# TwoStepPowerConversionBoard.net
KiCad netlist of a schematic drawn in EAGLE
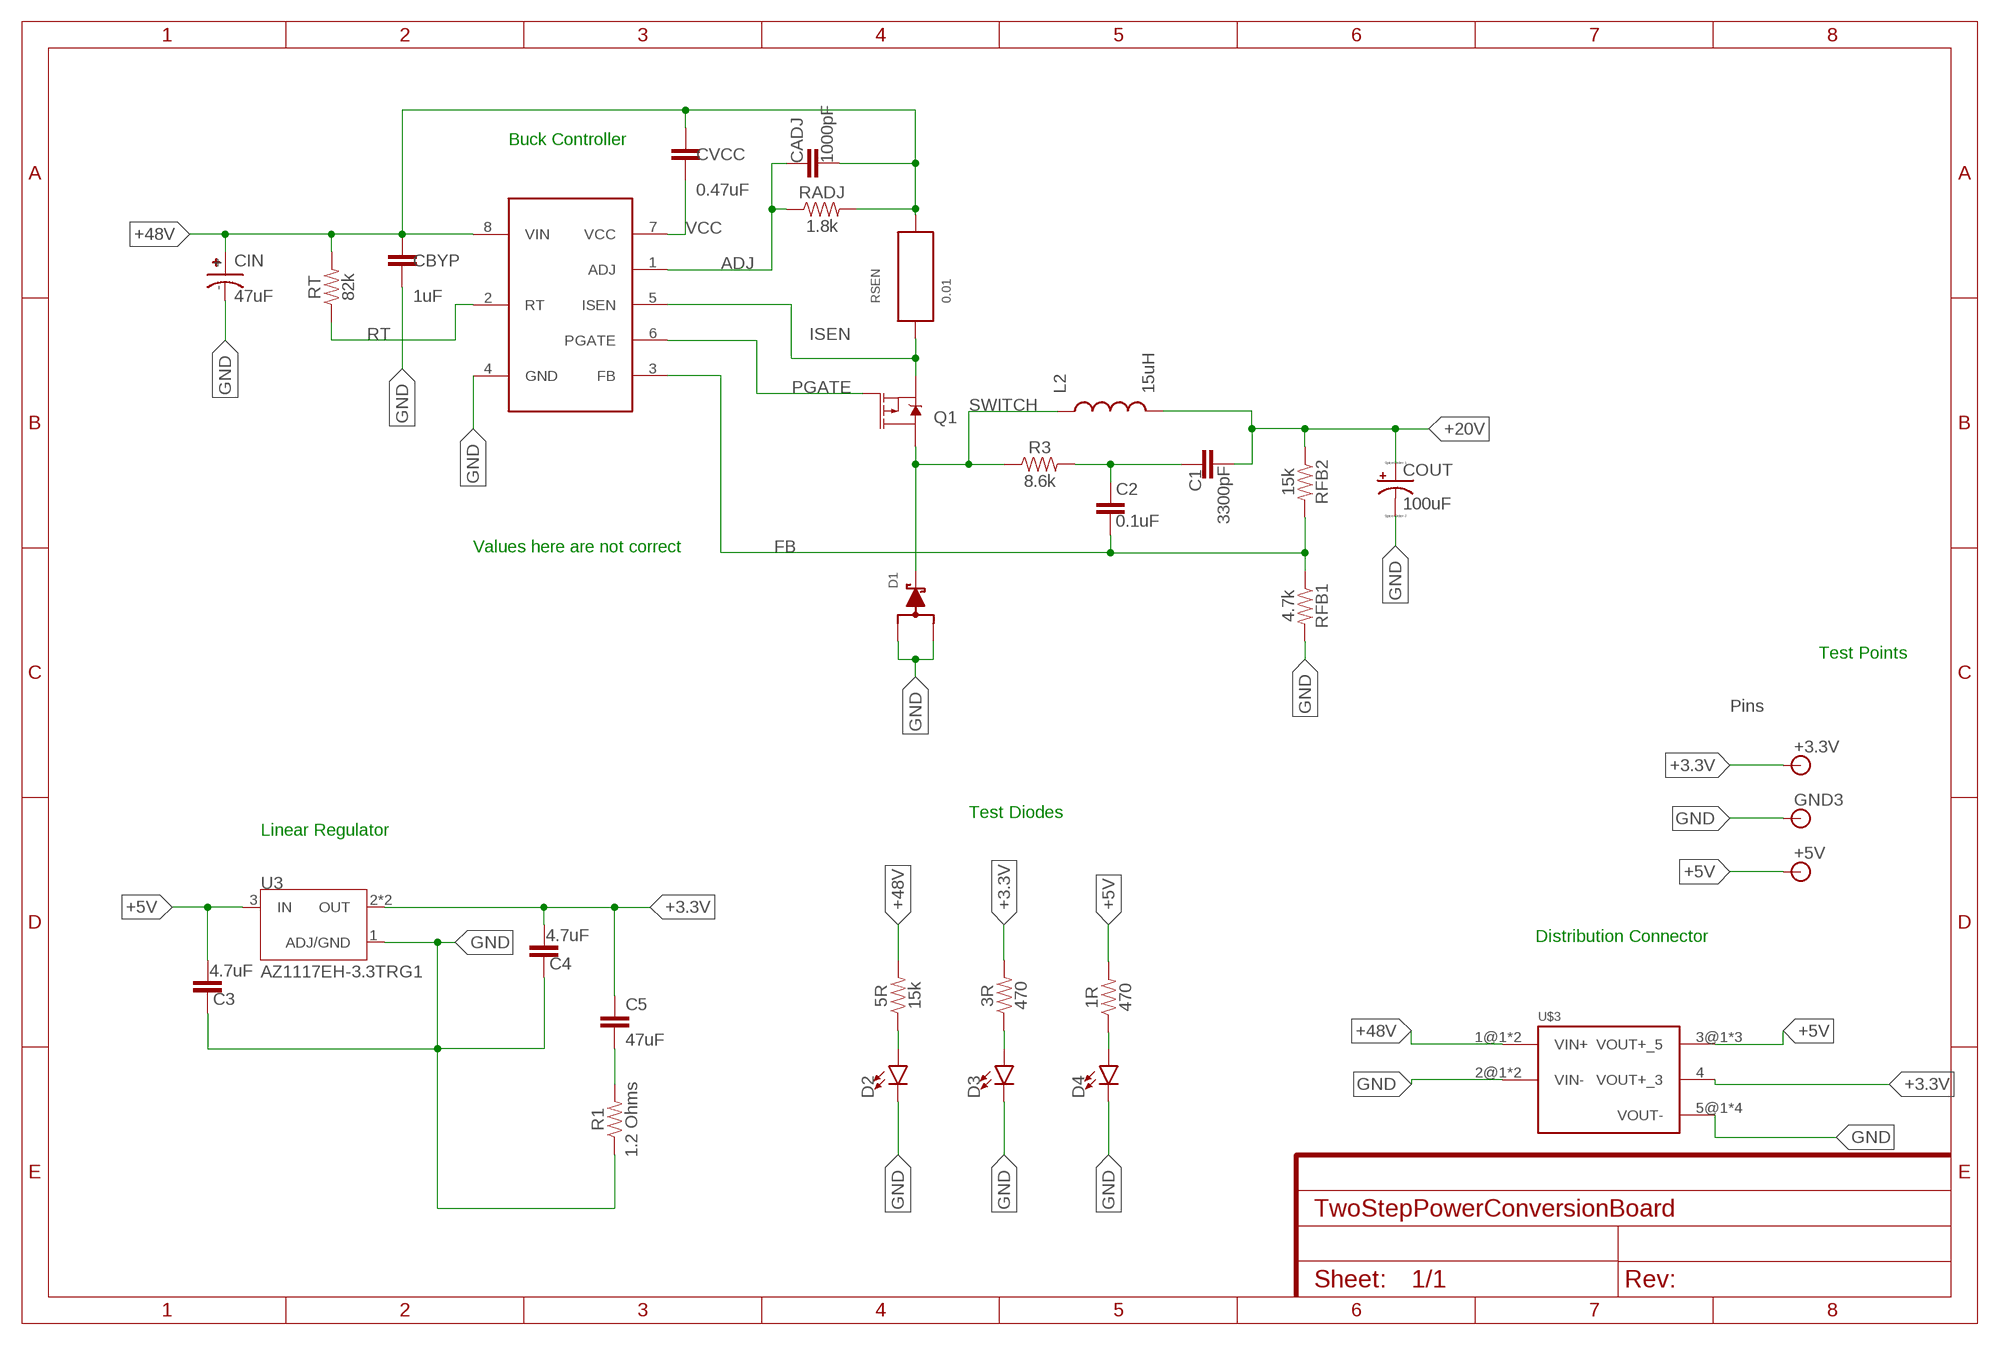
[diagram p0: schematic, sheet 1, part 1 of 2]
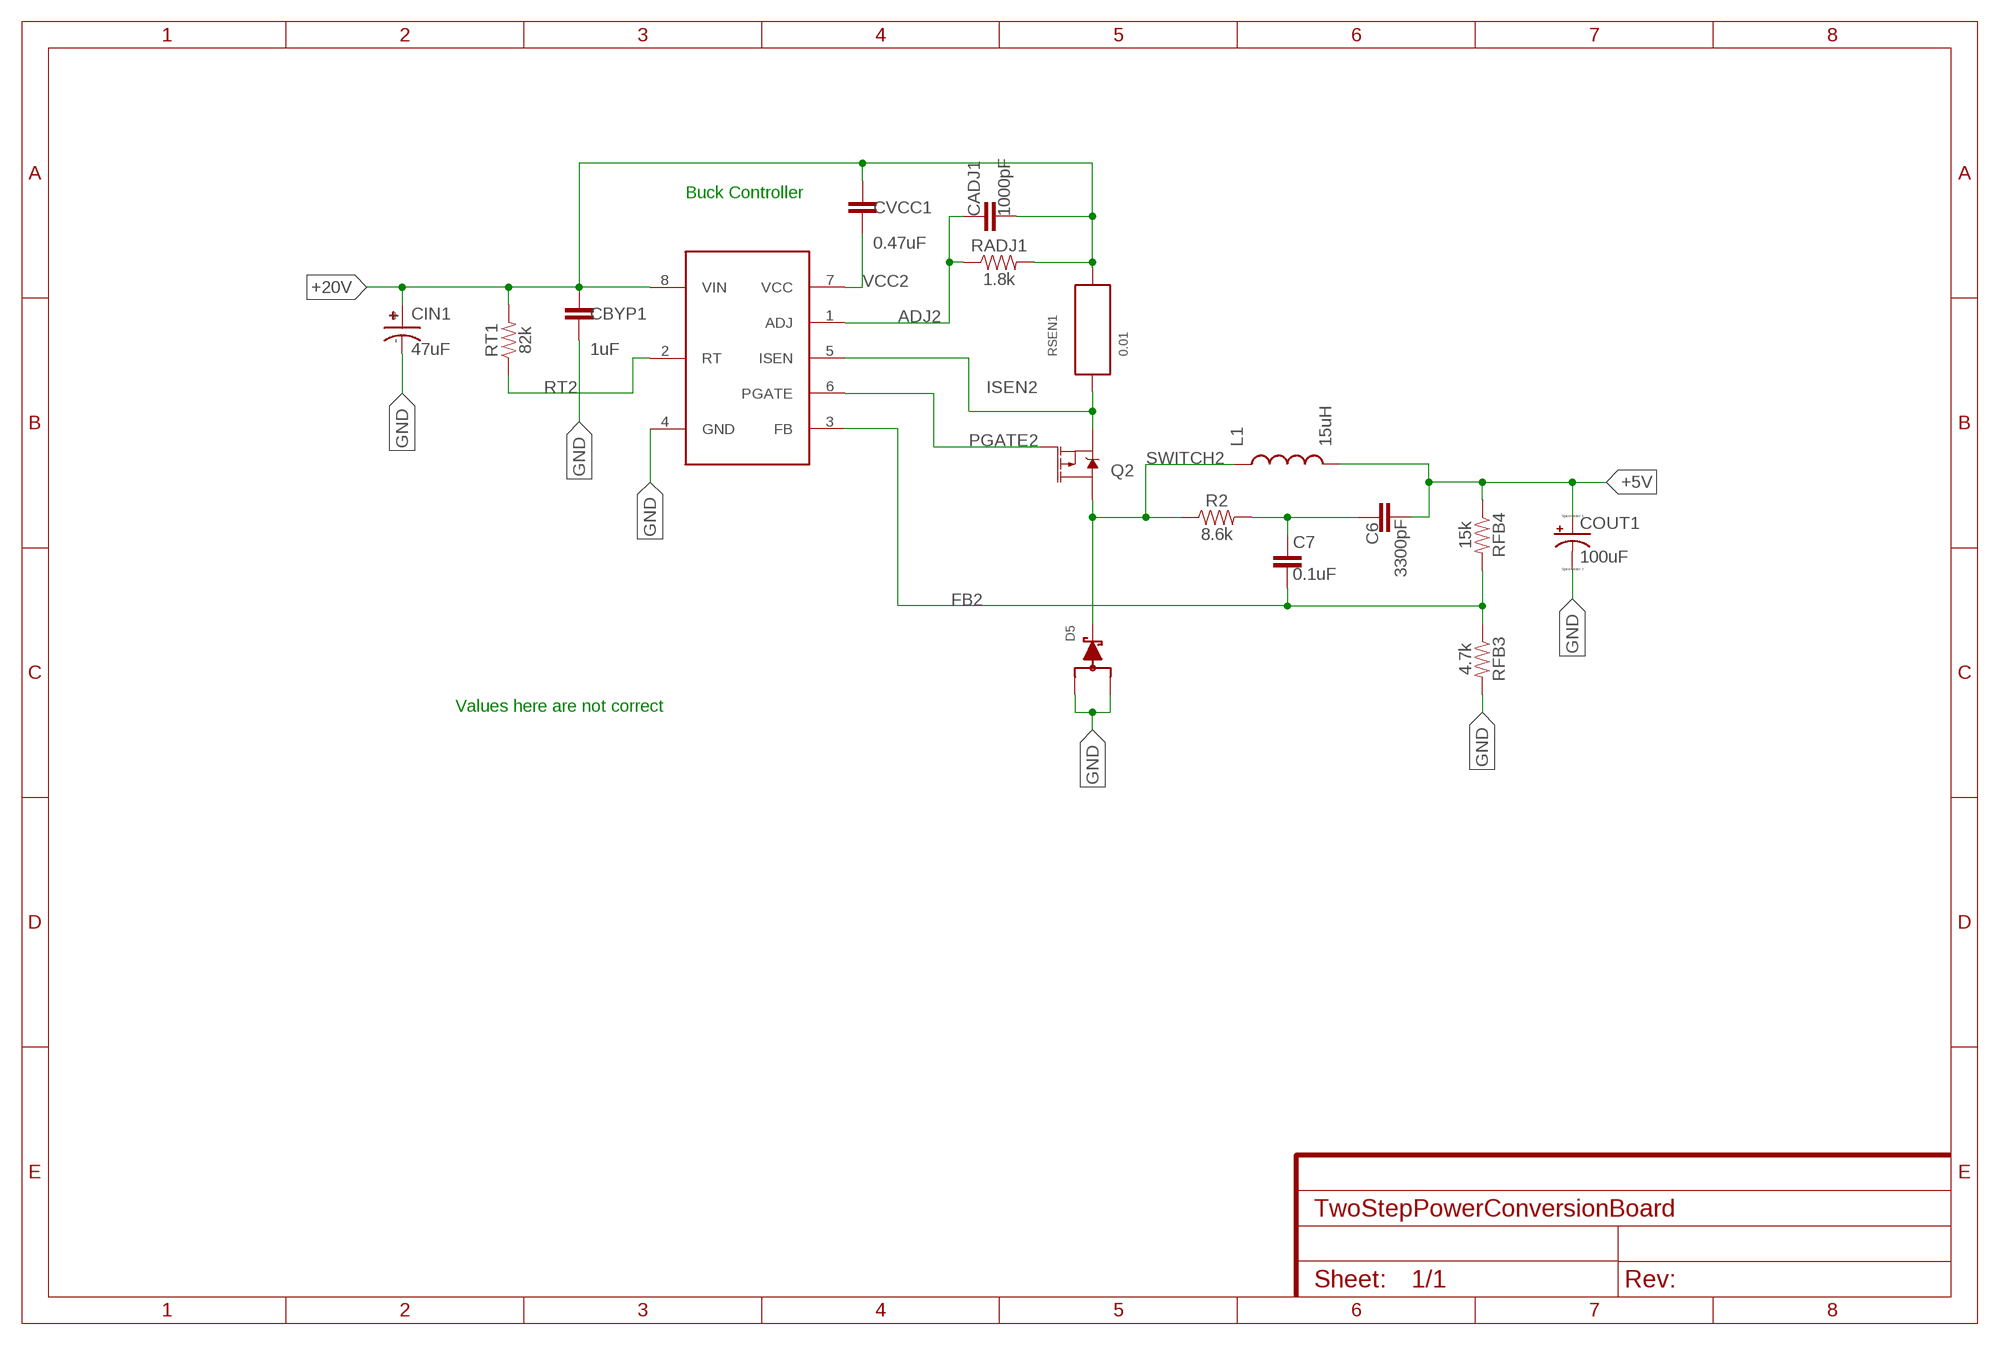
[diagram p1: schematic, sheet 1, part 2 of 2]

(export (version "E")
  (design (tool "Eeschema 10.0.6"))
  (components
    (comp (ref "+3.3V")
      (value "BANANA_CONN")
      (footprint "eagle-import:BANANA_CONN")
      (libsource (lib "eagle-import") (part "BANANA_CONN"))
    )
    (comp (ref "+5V")
      (value "BANANA_CONN")
      (footprint "eagle-import:BANANA_CONN")
      (libsource (lib "eagle-import") (part "BANANA_CONN"))
    )
    (comp (ref "1R")
      (value "470")
      (footprint "eagle-import:0603")
      (libsource (lib "eagle-import") (part "470OHM-0603-1/10W-1%"))
    )
    (comp (ref "3R")
      (value "470")
      (footprint "eagle-import:0603")
      (libsource (lib "eagle-import") (part "470OHM-0603-1/10W-1%"))
    )
    (comp (ref "5R")
      (value "15k")
      (footprint "eagle-import:0603")
      (libsource (lib "eagle-import") (part "470OHM-0603-1/10W-1%"))
    )
    (comp (ref "C1")
      (value "3300pF")
      (footprint "eagle-import:0603")
      (libsource (lib "eagle-import") (part "12PF-0603-50V-5%"))
    )
    (comp (ref "C2")
      (value "0.1uF")
      (footprint "eagle-import:0603")
      (libsource (lib "eagle-import") (part "12PF-0603-50V-5%"))
    )
    (comp (ref "C3")
      (value "4.7uF")
      (footprint "eagle-import:0603")
      (libsource (lib "eagle-import") (part "12PF-0603-50V-5%"))
    )
    (comp (ref "C4")
      (value "4.7uF")
      (footprint "eagle-import:0603")
      (libsource (lib "eagle-import") (part "12PF-0603-50V-5%"))
    )
    (comp (ref "C5")
      (value "47uF")
      (footprint "eagle-import:0603")
      (libsource (lib "eagle-import") (part "0.1UF-0603-25V-5%"))
    )
    (comp (ref "C6")
      (value "3300pF")
      (footprint "eagle-import:0603")
      (libsource (lib "eagle-import") (part "12PF-0603-50V-5%"))
    )
    (comp (ref "C7")
      (value "0.1uF")
      (footprint "eagle-import:0603")
      (libsource (lib "eagle-import") (part "12PF-0603-50V-5%"))
    )
    (comp (ref "CADJ")
      (value "1000pF")
      (footprint "eagle-import:0603")
      (libsource (lib "eagle-import") (part "5.6PF-0603-50V-5%"))
    )
    (comp (ref "CADJ1")
      (value "1000pF")
      (footprint "eagle-import:0603")
      (libsource (lib "eagle-import") (part "5.6PF-0603-50V-5%"))
    )
    (comp (ref "CBYP")
      (value "1uF")
      (footprint "eagle-import:0603")
      (libsource (lib "eagle-import") (part "3.3NF-0603-100V-10%"))
    )
    (comp (ref "CBYP1")
      (value "1uF")
      (footprint "eagle-import:0603")
      (libsource (lib "eagle-import") (part "3.3NF-0603-100V-10%"))
    )
    (comp (ref "CIN")
      (value "47uF")
      (footprint "eagle-import:CAPAE1030X1050N")
      (fields
        (field (name "ARROW_PART_NUMBER") "UCM1H331MNL1GS")
        (field (name "MOUSER_PART_NUMBER") "647-UCM1H331MNL1GS")
      )
      (libsource (lib "eagle-import") (part "UCM1H331MNL1GS"))
    )
    (comp (ref "CIN1")
      (value "47uF")
      (footprint "eagle-import:CAPAE1030X1050N")
      (fields
        (field (name "ARROW_PART_NUMBER") "UCM1H331MNL1GS")
        (field (name "MOUSER_PART_NUMBER") "647-UCM1H331MNL1GS")
      )
      (libsource (lib "eagle-import") (part "UCM1H331MNL1GS"))
    )
    (comp (ref "COUT")
      (value "100uF")
      (footprint "eagle-import:CTAN(7.30_4.30MM)")
      (libsource (lib "eagle-import") (part "C-TANTALUM(10UF_150UF)"))
    )
    (comp (ref "COUT1")
      (value "100uF")
      (footprint "eagle-import:CTAN(7.30_4.30MM)")
      (libsource (lib "eagle-import") (part "C-TANTALUM(10UF_150UF)"))
    )
    (comp (ref "CVCC")
      (value "0.47uF")
      (footprint "eagle-import:0603")
      (libsource (lib "eagle-import") (part "5.6PF-0603-50V-5%"))
    )
    (comp (ref "CVCC1")
      (value "0.47uF")
      (footprint "eagle-import:0603")
      (libsource (lib "eagle-import") (part "5.6PF-0603-50V-5%"))
    )
    (comp (ref "D1")
      (value "SWITCHMODE_SCHOTTKY")
      (footprint "eagle-import:DPAK-3")
      (libsource (lib "eagle-import") (part "SWITCHMODE_SCHOTTKY"))
    )
    (comp (ref "D2")
      (value "LED0603")
      (footprint "eagle-import:LED-0603")
      (libsource (lib "eagle-import") (part "LED0603"))
    )
    (comp (ref "D3")
      (value "LED0603")
      (footprint "eagle-import:LED-0603")
      (libsource (lib "eagle-import") (part "LED0603"))
    )
    (comp (ref "D4")
      (value "LED0603")
      (footprint "eagle-import:LED-0603")
      (libsource (lib "eagle-import") (part "LED0603"))
    )
    (comp (ref "D5")
      (value "SWITCHMODE_SCHOTTKY")
      (footprint "eagle-import:DPAK-3")
      (libsource (lib "eagle-import") (part "SWITCHMODE_SCHOTTKY"))
    )
    (comp (ref "GND3")
      (value "BANANA_CONN")
      (footprint "eagle-import:BANANA_CONN")
      (libsource (lib "eagle-import") (part "BANANA_CONN"))
    )
    (comp (ref "L1")
      (value "15uH")
      (footprint "eagle-import:HCMA1305")
      (libsource (lib "eagle-import") (part "HCMA1305"))
    )
    (comp (ref "L2")
      (value "15uH")
      (footprint "eagle-import:HCMA1305")
      (libsource (lib "eagle-import") (part "HCMA1305"))
    )
    (comp (ref "Q1")
      (value "MOSFET_PCH-NDS8434")
      (footprint "eagle-import:SO08")
      (libsource (lib "eagle-import") (part "MOSFET_PCH-NDS8434"))
    )
    (comp (ref "Q2")
      (value "MOSFET_PCH-NDS8434")
      (footprint "eagle-import:SO08")
      (libsource (lib "eagle-import") (part "MOSFET_PCH-NDS8434"))
    )
    (comp (ref "R1")
      (value "1.2 Ohms")
      (footprint "eagle-import:0603")
      (libsource (lib "eagle-import") (part "1.6KOHM-0603-1/10W-1%"))
    )
    (comp (ref "R2")
      (value "8.6k")
      (footprint "eagle-import:0603")
      (libsource (lib "eagle-import") (part "RESISTOR0603"))
    )
    (comp (ref "R3")
      (value "8.6k")
      (footprint "eagle-import:0603")
      (libsource (lib "eagle-import") (part "RESISTOR0603"))
    )
    (comp (ref "RADJ")
      (value "1.8k")
      (footprint "eagle-import:0603")
      (libsource (lib "eagle-import") (part "RESISTOR0603"))
    )
    (comp (ref "RADJ1")
      (value "1.8k")
      (footprint "eagle-import:0603")
      (libsource (lib "eagle-import") (part "RESISTOR0603"))
    )
    (comp (ref "RFB1")
      (value "4.7k")
      (footprint "eagle-import:0603")
      (libsource (lib "eagle-import") (part "RESISTOR0603"))
    )
    (comp (ref "RFB2")
      (value "15k")
      (footprint "eagle-import:0603")
      (libsource (lib "eagle-import") (part "RESISTOR0603"))
    )
    (comp (ref "RFB3")
      (value "4.7k")
      (footprint "eagle-import:0603")
      (libsource (lib "eagle-import") (part "RESISTOR0603"))
    )
    (comp (ref "RFB4")
      (value "15k")
      (footprint "eagle-import:0603")
      (libsource (lib "eagle-import") (part "RESISTOR0603"))
    )
    (comp (ref "RSEN")
      (value "0.01")
      (footprint "eagle-import:CSS2H-2512")
      (libsource (lib "eagle-import") (part "CSS2H-2512"))
    )
    (comp (ref "RSEN1")
      (value "0.01")
      (footprint "eagle-import:CSS2H-2512")
      (libsource (lib "eagle-import") (part "CSS2H-2512"))
    )
    (comp (ref "RT")
      (value "82k")
      (footprint "eagle-import:0603")
      (libsource (lib "eagle-import") (part "82OHM-0603-1/10W-1%"))
    )
    (comp (ref "RT1")
      (value "82k")
      (footprint "eagle-import:0603")
      (libsource (lib "eagle-import") (part "82OHM-0603-1/10W-1%"))
    )
    (comp (ref "U$1")
      (value "LM5085")
      (footprint "eagle-import:LM5085")
      (libsource (lib "eagle-import") (part "LM5085"))
    )
    (comp (ref "U$2")
      (value "LM5085")
      (footprint "eagle-import:LM5085")
      (libsource (lib "eagle-import") (part "LM5085"))
    )
    (comp (ref "U$3")
      (value "CON2DIST")
      (footprint "eagle-import:CON2DIST")
      (libsource (lib "eagle-import") (part "CON2DIST"))
    )
    (comp (ref "U3")
      (value "AZ1117EH-3.3TRG1")
      (footprint "eagle-import:SOT230P700X180-4N")
      (fields (field (name "MF") "Diodes Inc."))
      (libsource (lib "eagle-import") (part "AZ1117EH-3.3TRG1"))
    )
  )
  (nets
    (net (code "1") (name "+3.3V") (class "Default")
      (node (ref "+3.3V") (pin "P$1") (pinfunction "1_P$1") (pintype "passive"))
      (node (ref "3R") (pin "2") (pinfunction "2_2") (pintype "passive"))
      (node (ref "C4") (pin "1") (pinfunction "1_1") (pintype "passive"))
      (node (ref "C5") (pin "1") (pinfunction "1_1") (pintype "passive"))
      (node (ref "U$3") (pin "4") (pinfunction "VOUT+_3_4") (pintype "bidirectional"))
      (node (ref "U3") (pin "2") (pinfunction "OUT_2") (pintype "output"))
      (node (ref "U3") (pin "4") (pinfunction "OUT_4") (pintype "output"))
    )
    (net (code "2") (name "+5V") (class "Default")
      (node (ref "+5V") (pin "P$1") (pinfunction "1_P$1") (pintype "passive"))
      (node (ref "1R") (pin "2") (pinfunction "2_2") (pintype "passive"))
      (node (ref "C3") (pin "1") (pinfunction "1_1") (pintype "passive"))
      (node (ref "C6") (pin "1") (pinfunction "1_1") (pintype "passive"))
      (node (ref "COUT1") (pin "+") (pinfunction "+_+") (pintype "passive"))
      (node (ref "L1") (pin "2") (pinfunction "2_2") (pintype "passive"))
      (node (ref "RFB4") (pin "1") (pinfunction "1_1") (pintype "passive"))
      (node (ref "U$3") (pin "3@1") (pinfunction "VOUT+_5_3@1") (pintype "bidirectional"))
      (node (ref "U$3") (pin "3@2") (pinfunction "VOUT+_5_3@2") (pintype "bidirectional"))
      (node (ref "U$3") (pin "3@3") (pinfunction "VOUT+_5_3@3") (pintype "bidirectional"))
      (node (ref "U3") (pin "3") (pinfunction "IN_3") (pintype "input"))
    )
    (net (code "3") (name "+20V") (class "Default")
      (node (ref "C1") (pin "1") (pinfunction "1_1") (pintype "passive"))
      (node (ref "CADJ1") (pin "2") (pinfunction "2_2") (pintype "passive"))
      (node (ref "CBYP1") (pin "1") (pinfunction "1_1") (pintype "passive"))
      (node (ref "CIN1") (pin "+") (pinfunction "+_+") (pintype "bidirectional"))
      (node (ref "COUT") (pin "+") (pinfunction "+_+") (pintype "passive"))
      (node (ref "CVCC1") (pin "1") (pinfunction "1_1") (pintype "passive"))
      (node (ref "L2") (pin "2") (pinfunction "2_2") (pintype "passive"))
      (node (ref "RADJ1") (pin "2") (pinfunction "2_2") (pintype "passive"))
      (node (ref "RFB2") (pin "1") (pinfunction "1_1") (pintype "passive"))
      (node (ref "RSEN1") (pin "2") (pinfunction "2_2") (pintype "bidirectional"))
      (node (ref "RT1") (pin "2") (pinfunction "2_2") (pintype "passive"))
      (node (ref "U$2") (pin "8") (pinfunction "VIN_8") (pintype "bidirectional"))
    )
    (net (code "4") (name "+48V") (class "Default")
      (node (ref "5R") (pin "2") (pinfunction "2_2") (pintype "passive"))
      (node (ref "CADJ") (pin "2") (pinfunction "2_2") (pintype "passive"))
      (node (ref "CBYP") (pin "1") (pinfunction "1_1") (pintype "passive"))
      (node (ref "CIN") (pin "+") (pinfunction "+_+") (pintype "bidirectional"))
      (node (ref "CVCC") (pin "1") (pinfunction "1_1") (pintype "passive"))
      (node (ref "RADJ") (pin "2") (pinfunction "2_2") (pintype "passive"))
      (node (ref "RSEN") (pin "2") (pinfunction "2_2") (pintype "bidirectional"))
      (node (ref "RT") (pin "2") (pinfunction "2_2") (pintype "passive"))
      (node (ref "U$1") (pin "8") (pinfunction "VIN_8") (pintype "bidirectional"))
      (node (ref "U$3") (pin "1@1") (pinfunction "VIN+_1@1") (pintype "bidirectional"))
      (node (ref "U$3") (pin "1@2") (pinfunction "VIN+_1@2") (pintype "bidirectional"))
    )
    (net (code "5") (name "/ADJ") (class "Default")
      (node (ref "CADJ") (pin "1") (pinfunction "1_1") (pintype "passive"))
      (node (ref "RADJ") (pin "1") (pinfunction "1_1") (pintype "passive"))
      (node (ref "U$1") (pin "1") (pinfunction "ADJ_1") (pintype "bidirectional"))
    )
    (net (code "6") (name "/ADJ2") (class "Default")
      (node (ref "CADJ1") (pin "1") (pinfunction "1_1") (pintype "passive"))
      (node (ref "RADJ1") (pin "1") (pinfunction "1_1") (pintype "passive"))
      (node (ref "U$2") (pin "1") (pinfunction "ADJ_1") (pintype "bidirectional"))
    )
    (net (code "7") (name "/FB") (class "Default")
      (node (ref "C2") (pin "2") (pinfunction "2_2") (pintype "passive"))
      (node (ref "RFB1") (pin "1") (pinfunction "1_1") (pintype "passive"))
      (node (ref "RFB2") (pin "2") (pinfunction "2_2") (pintype "passive"))
      (node (ref "U$1") (pin "3") (pinfunction "FB_3") (pintype "bidirectional"))
    )
    (net (code "8") (name "/FB2") (class "Default")
      (node (ref "C7") (pin "2") (pinfunction "2_2") (pintype "passive"))
      (node (ref "RFB3") (pin "1") (pinfunction "1_1") (pintype "passive"))
      (node (ref "RFB4") (pin "2") (pinfunction "2_2") (pintype "passive"))
      (node (ref "U$2") (pin "3") (pinfunction "FB_3") (pintype "bidirectional"))
    )
    (net (code "9") (name "/ISEN") (class "Default")
      (node (ref "Q1") (pin "1") (pinfunction "S_1") (pintype "bidirectional"))
      (node (ref "Q1") (pin "2") (pinfunction "S_2") (pintype "bidirectional"))
      (node (ref "Q1") (pin "3") (pinfunction "S_3") (pintype "bidirectional"))
      (node (ref "RSEN") (pin "1") (pinfunction "1_1") (pintype "bidirectional"))
      (node (ref "U$1") (pin "5") (pinfunction "ISEN_5") (pintype "bidirectional"))
    )
    (net (code "10") (name "/ISEN2") (class "Default")
      (node (ref "Q2") (pin "1") (pinfunction "S_1") (pintype "bidirectional"))
      (node (ref "Q2") (pin "2") (pinfunction "S_2") (pintype "bidirectional"))
      (node (ref "Q2") (pin "3") (pinfunction "S_3") (pintype "bidirectional"))
      (node (ref "RSEN1") (pin "1") (pinfunction "1_1") (pintype "bidirectional"))
      (node (ref "U$2") (pin "5") (pinfunction "ISEN_5") (pintype "bidirectional"))
    )
    (net (code "11") (name "/PGATE") (class "Default")
      (node (ref "Q1") (pin "4") (pinfunction "G_4") (pintype "bidirectional"))
      (node (ref "U$1") (pin "6") (pinfunction "PGATE_6") (pintype "bidirectional"))
    )
    (net (code "12") (name "/PGATE2") (class "Default")
      (node (ref "Q2") (pin "4") (pinfunction "G_4") (pintype "bidirectional"))
      (node (ref "U$2") (pin "6") (pinfunction "PGATE_6") (pintype "bidirectional"))
    )
    (net (code "13") (name "/RT") (class "Default")
      (node (ref "RT") (pin "1") (pinfunction "1_1") (pintype "passive"))
      (node (ref "U$1") (pin "2") (pinfunction "RT_2") (pintype "bidirectional"))
    )
    (net (code "14") (name "/RT2") (class "Default")
      (node (ref "RT1") (pin "1") (pinfunction "1_1") (pintype "passive"))
      (node (ref "U$2") (pin "2") (pinfunction "RT_2") (pintype "bidirectional"))
    )
    (net (code "15") (name "/SWITCH") (class "Default")
      (node (ref "D1") (pin "4") (pinfunction "C_4") (pintype "bidirectional"))
      (node (ref "L2") (pin "1") (pinfunction "1_1") (pintype "passive"))
      (node (ref "Q1") (pin "5") (pinfunction "D_5") (pintype "bidirectional"))
      (node (ref "Q1") (pin "6") (pinfunction "D_6") (pintype "bidirectional"))
      (node (ref "Q1") (pin "7") (pinfunction "D_7") (pintype "bidirectional"))
      (node (ref "Q1") (pin "8") (pinfunction "D_8") (pintype "bidirectional"))
      (node (ref "R3") (pin "1") (pinfunction "1_1") (pintype "passive"))
    )
    (net (code "16") (name "/SWITCH2") (class "Default")
      (node (ref "D5") (pin "4") (pinfunction "C_4") (pintype "bidirectional"))
      (node (ref "L1") (pin "1") (pinfunction "1_1") (pintype "passive"))
      (node (ref "Q2") (pin "5") (pinfunction "D_5") (pintype "bidirectional"))
      (node (ref "Q2") (pin "6") (pinfunction "D_6") (pintype "bidirectional"))
      (node (ref "Q2") (pin "7") (pinfunction "D_7") (pintype "bidirectional"))
      (node (ref "Q2") (pin "8") (pinfunction "D_8") (pintype "bidirectional"))
      (node (ref "R2") (pin "1") (pinfunction "1_1") (pintype "passive"))
    )
    (net (code "17") (name "/VCC") (class "Default")
      (node (ref "CVCC") (pin "2") (pinfunction "2_2") (pintype "passive"))
      (node (ref "U$1") (pin "7") (pinfunction "VCC_7") (pintype "bidirectional"))
    )
    (net (code "18") (name "/VCC2") (class "Default")
      (node (ref "CVCC1") (pin "2") (pinfunction "2_2") (pintype "passive"))
      (node (ref "U$2") (pin "7") (pinfunction "VCC_7") (pintype "bidirectional"))
    )
    (net (code "19") (name "GND") (class "Default")
      (node (ref "C3") (pin "2") (pinfunction "2_2") (pintype "passive"))
      (node (ref "C4") (pin "2") (pinfunction "2_2") (pintype "passive"))
      (node (ref "CBYP") (pin "2") (pinfunction "2_2") (pintype "passive"))
      (node (ref "CBYP1") (pin "2") (pinfunction "2_2") (pintype "passive"))
      (node (ref "CIN") (pin "-") (pinfunction "-_-") (pintype "bidirectional"))
      (node (ref "CIN1") (pin "-") (pinfunction "-_-") (pintype "bidirectional"))
      (node (ref "COUT") (pin "-") (pinfunction "-_-") (pintype "passive"))
      (node (ref "COUT1") (pin "-") (pinfunction "-_-") (pintype "passive"))
      (node (ref "D1") (pin "1") (pinfunction "A_1") (pintype "bidirectional"))
      (node (ref "D1") (pin "3") (pinfunction "A_3") (pintype "bidirectional"))
      (node (ref "D2") (pin "C") (pinfunction "C_C") (pintype "passive"))
      (node (ref "D3") (pin "C") (pinfunction "C_C") (pintype "passive"))
      (node (ref "D4") (pin "C") (pinfunction "C_C") (pintype "passive"))
      (node (ref "D5") (pin "1") (pinfunction "A_1") (pintype "bidirectional"))
      (node (ref "D5") (pin "3") (pinfunction "A_3") (pintype "bidirectional"))
      (node (ref "GND3") (pin "P$1") (pinfunction "1_P$1") (pintype "passive"))
      (node (ref "R1") (pin "1") (pinfunction "1_1") (pintype "passive"))
      (node (ref "RFB1") (pin "2") (pinfunction "2_2") (pintype "passive"))
      (node (ref "RFB3") (pin "2") (pinfunction "2_2") (pintype "passive"))
      (node (ref "U$1") (pin "4") (pinfunction "GND_4") (pintype "bidirectional"))
      (node (ref "U$2") (pin "4") (pinfunction "GND_4") (pintype "bidirectional"))
      (node (ref "U$3") (pin "2@1") (pinfunction "VIN-_2@1") (pintype "bidirectional"))
      (node (ref "U$3") (pin "2@2") (pinfunction "VIN-_2@2") (pintype "bidirectional"))
      (node (ref "U$3") (pin "5@1") (pinfunction "VOUT-_5@1") (pintype "bidirectional"))
      (node (ref "U$3") (pin "5@2") (pinfunction "VOUT-_5@2") (pintype "bidirectional"))
      (node (ref "U$3") (pin "5@3") (pinfunction "VOUT-_5@3") (pintype "bidirectional"))
      (node (ref "U$3") (pin "5@4") (pinfunction "VOUT-_5@4") (pintype "bidirectional"))
      (node (ref "U3") (pin "1") (pinfunction "ADJ/GND_1") (pintype "power_in"))
    )
    (net (code "20") (name "Net-(1R-Pad1)") (class "Default")
      (node (ref "1R") (pin "1") (pinfunction "1_1") (pintype "passive"))
      (node (ref "D4") (pin "A") (pinfunction "A_A") (pintype "passive"))
    )
    (net (code "21") (name "Net-(3R-Pad1)") (class "Default")
      (node (ref "3R") (pin "1") (pinfunction "1_1") (pintype "passive"))
      (node (ref "D3") (pin "A") (pinfunction "A_A") (pintype "passive"))
    )
    (net (code "22") (name "Net-(5R-Pad1)") (class "Default")
      (node (ref "5R") (pin "1") (pinfunction "1_1") (pintype "passive"))
      (node (ref "D2") (pin "A") (pinfunction "A_A") (pintype "passive"))
    )
    (net (code "23") (name "Net-(C1-Pad2)") (class "Default")
      (node (ref "C1") (pin "2") (pinfunction "2_2") (pintype "passive"))
      (node (ref "C2") (pin "1") (pinfunction "1_1") (pintype "passive"))
      (node (ref "R3") (pin "2") (pinfunction "2_2") (pintype "passive"))
    )
    (net (code "24") (name "Net-(C5-Pad2)") (class "Default")
      (node (ref "C5") (pin "2") (pinfunction "2_2") (pintype "passive"))
      (node (ref "R1") (pin "2") (pinfunction "2_2") (pintype "passive"))
    )
    (net (code "25") (name "Net-(C6-Pad2)") (class "Default")
      (node (ref "C6") (pin "2") (pinfunction "2_2") (pintype "passive"))
      (node (ref "C7") (pin "1") (pinfunction "1_1") (pintype "passive"))
      (node (ref "R2") (pin "2") (pinfunction "2_2") (pintype "passive"))
    )
  )
)
